# CP_Scheme.net
KiCad netlist of a schematic drawn in Altium Designer
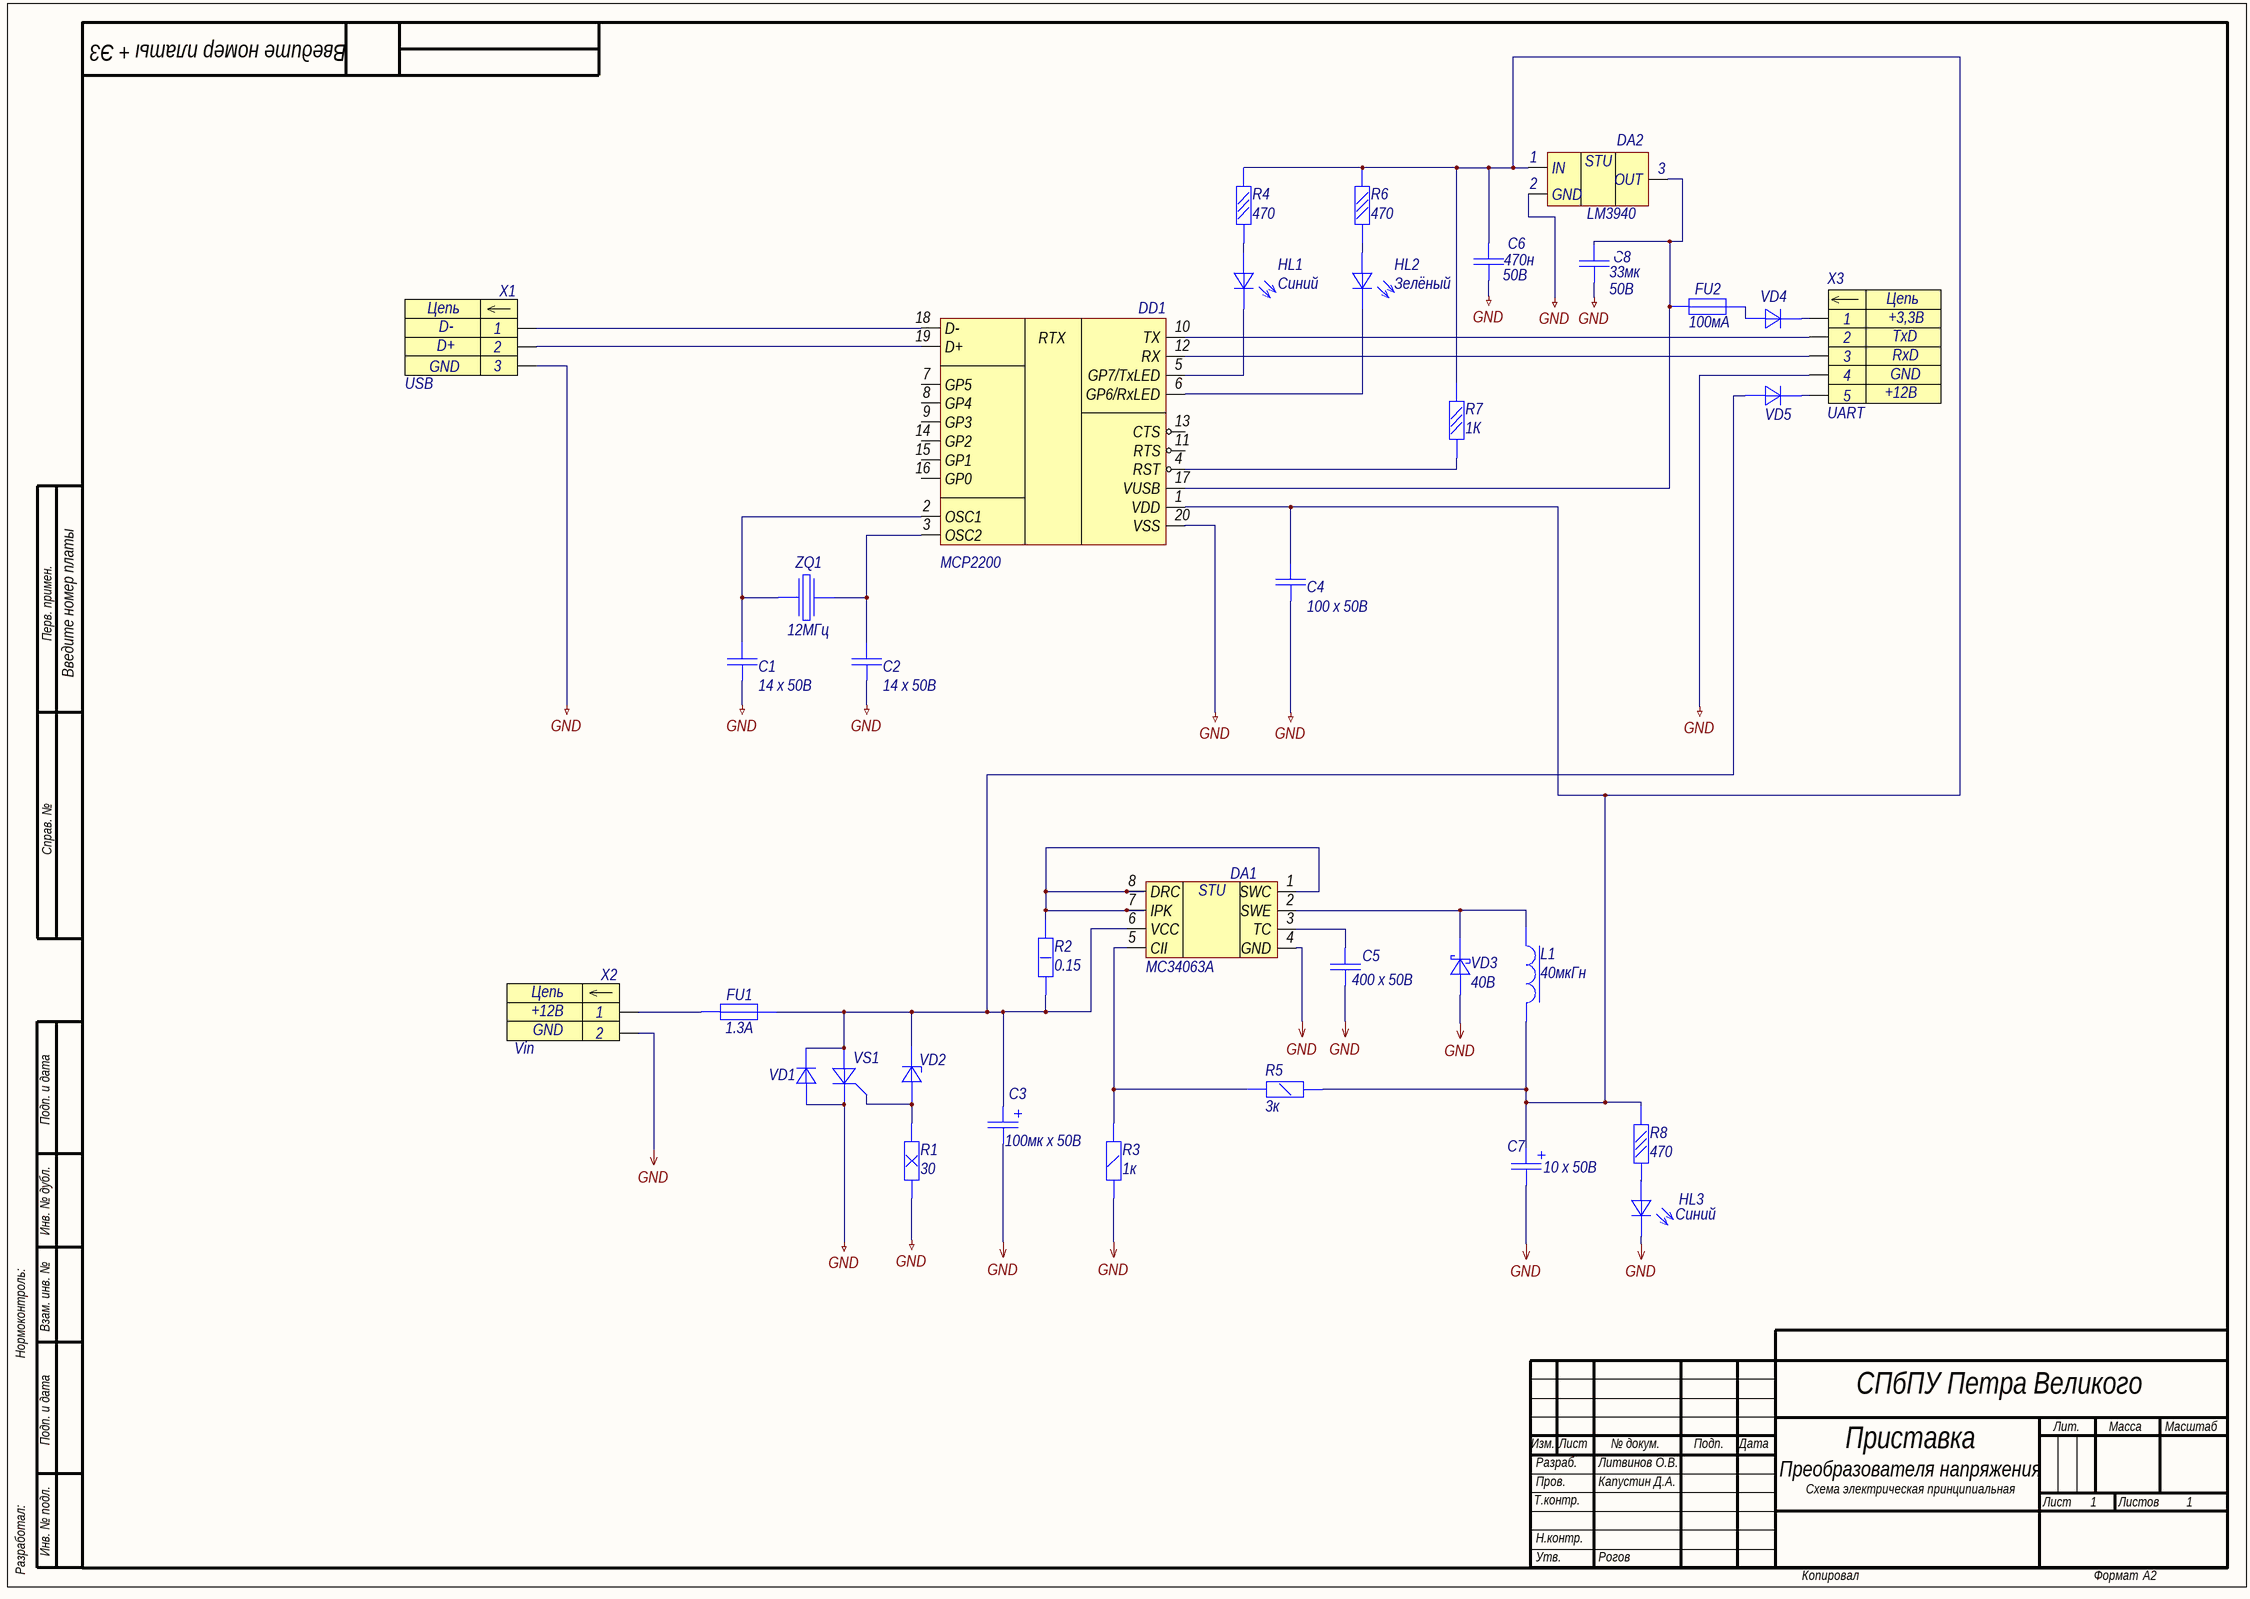
[diagram p0: CP_Scheme.SchDoc]

(export (version "E")
  (design (tool "Eeschema 10.0.6"))
  (components
    (comp (ref "C1")
      (value "14 х 50В")
      (footprint "C0805")
      (fields (field (name "Comment") "Capacitor"))
      (libsource (lib "") (part "Capacitor_1"))
    )
    (comp (ref "C2")
      (value "14 х 50В")
      (footprint "C0805")
      (fields (field (name "Comment") "Capacitor"))
      (libsource (lib "") (part "Capacitor_1"))
    )
    (comp (ref "C3")
      (value "Capacitor-E")
      (footprint "C1206")
      (fields (field (name "ЁМКОСТЬ") "100мк х 50В") (field (name "PUBLISHER") "Олег Литвинов"))
      (libsource (lib "Capacitor GOST") (part "Capacitor-E"))
    )
    (comp (ref "C4")
      (value "100 х 50В")
      (footprint "C0805")
      (fields (field (name "Comment") "Capacitor"))
      (libsource (lib "Capacitor_GOST") (part "Capacitor"))
    )
    (comp (ref "C5")
      (value "Capacitor")
      (footprint "R0805")
      (fields (field (name "ЁМКОСТЬ") "400 х 50В") (field (name "PUBLISHER") "Andrew Danich"))
      (libsource (lib "Capacitor GOST") (part "Capacitor"))
    )
    (comp (ref "C6")
      (value "470н")
      (footprint "C0805")
      (fields (field (name "VOLTAGE") "50В") (field (name "Comment") "Capacitor"))
      (libsource (lib "Capacitor_GOST") (part "Capacitor"))
    )
    (comp (ref "C7")
      (value "Capacitor-E")
      (footprint "C1206")
      (fields (field (name "ЁМКОСТЬ") "10 х 50В") (field (name "PUBLISHER") "Олег Литвинов"))
      (libsource (lib "Capacitor GOST") (part "Capacitor-E"))
    )
    (comp (ref "C8")
      (value "33мк")
      (footprint "C0805")
      (fields (field (name "VOLTAGE") "50В") (field (name "Comment") "Capacitor"))
      (libsource (lib "Capacitor_GOST") (part "Capacitor"))
    )
    (comp (ref "DA1")
      (value "MC34063A")
      (footprint "PCBComponent_1")
      (libsource (lib "MCP2200_UART_USB") (part "MC34063A"))
    )
    (comp (ref "DA2")
      (value "LM3940")
      (footprint "SOT95P237X112-3N")
      (fields (field (name "ITEM ID") "LM3940"))
      (libsource (lib "MCP2200_UART_USB") (part "LM3940"))
    )
    (comp (ref "DD1")
      (value "MCP2200")
      (footprint "SOIC127P1030X265-20N")
      (fields (field (name "WTF") "RTX") (field (name "CREATE") "Litvinov"))
      (libsource (lib "Schlib1") (part "MCP2200"))
    )
    (comp (ref "FU1")
      (value "1.3A")
      (footprint "F1812")
      (fields (field (name "Comment") "Fuse"))
      (libsource (lib "Fuse_GOST") (part "Fuse"))
    )
    (comp (ref "FU2")
      (value "100мA")
      (footprint "F1812")
      (fields (field (name "Comment") "Fuse"))
      (libsource (lib "Fuse_GOST") (part "Fuse"))
    )
    (comp (ref "HL1")
      (value "LED_3V")
      (footprint "LD0805")
      (fields (field (name "ЦВЕТ") "Синий") (field (name "PUBLISHER") "Andrew Danich"))
      (libsource (lib "") (part "Led-1_1"))
    )
    (comp (ref "HL2")
      (value "LED_3V")
      (footprint "LD0805")
      (fields (field (name "ЦВЕТ") "Зелёный") (field (name "PUBLISHER") "Andrew Danich"))
      (libsource (lib "") (part "Led-1_1"))
    )
    (comp (ref "HL3")
      (value "LED_3V")
      (footprint "LD0805")
      (fields (field (name "ЦВЕТ") "Синий") (field (name "PUBLISHER") "Andrew Danich"))
      (libsource (lib "Led GOST") (part "Led-1"))
    )
    (comp (ref "L1")
      (value "40мкГн")
      (footprint "МДГ-2")
      (fields
        (field (name "PART NUMBER") "КИВ18-100")
        (field (name "TOLERANCE") "±10%")
        (field (name "MANUFACTURER") "ОАО \"МСТАТОР\"")
        (field (name "PUBLISHER") "Andrew Danich")
      )
      (libsource (lib "Lib_GOST") (part "Coil"))
    )
    (comp (ref "R1")
      (value "Resistor_10,0W")
      (footprint "R0805")
      (fields (field (name "СОПРОТИВЛЕНИЕ") "30"))
      (libsource (lib "Resistor_GOST") (part "Resistor_10,0W"))
    )
    (comp (ref "R2")
      (value "0.15")
      (footprint "R0805")
      (fields (field (name "Comment") "Resistor_1,0W"))
      (libsource (lib "Resistor_GOST") (part "Resistor_1,0W"))
    )
    (comp (ref "R3")
      (value "1к")
      (footprint "R0805")
      (fields (field (name "Comment") "Resistor_0,25W"))
      (libsource (lib "Resistor_GOST") (part "Resistor_0,25W"))
    )
    (comp (ref "R4")
      (value "Resistor_0,05W")
      (footprint "R0805")
      (fields (field (name "СОПРОТИВЛЕНИЕ") "470"))
      (libsource (lib "Resistor_GOST") (part "Resistor_0,05W"))
    )
    (comp (ref "R5")
      (value "3к")
      (footprint "R0805")
      (fields (field (name "Comment") "Resistor_0,25W"))
      (libsource (lib "Resistor_GOST") (part "Resistor_0,25W"))
    )
    (comp (ref "R6")
      (value "Resistor_0,05W")
      (footprint "R0805")
      (fields (field (name "СОПРОТИВЛЕНИЕ") "470"))
      (libsource (lib "Resistor_GOST") (part "Resistor_0,05W"))
    )
    (comp (ref "R7")
      (value "1К")
      (footprint "R0805")
      (fields (field (name "Comment") "Resistor_0,05W"))
      (libsource (lib "") (part "Resistor_0,05W_1"))
    )
    (comp (ref "R8")
      (value "Resistor_0,05W")
      (footprint "R0805")
      (fields (field (name "СОПРОТИВЛЕНИЕ") "470"))
      (libsource (lib "Resistor_GOST") (part "Resistor_0,05W"))
    )
    (comp (ref "VD1") (value "Diode") (footprint "SOD-123") (libsource (lib "Diode_GOST") (part "Diode")))
    (comp (ref "VD2")
      (value "Suppressor")
      (footprint "DO-214AA")
      (libsource (lib "Diode_GOST") (part "Suppressor"))
    )
    (comp (ref "VD3")
      (value "Schottky")
      (footprint "DO-214AC")
      (description "BYV10-40")
      (fields (field (name "МАКСИМАЛЬНОЕ ОБРАТНОЕ НАПРЯЖЕНИЕ") "40В"))
      (libsource (lib "Diode_GOST") (part "Schottky"))
    )
    (comp (ref "VD4") (value "Diode") (footprint "SOD-123") (libsource (lib "") (part "Diode_2")))
    (comp (ref "VD5") (value "Diode") (footprint "SOD-123") (libsource (lib "") (part "Diode_1")))
    (comp (ref "VS1")
      (value "tiristor")
      (footprint "SOT95P237X112-3N")
      (libsource (lib "Schlib1") (part "tiristor"))
    )
    (comp (ref "X1")
      (value "USB")
      (footprint "DS1099")
      (fields
        (field (name "OUT") "D-")
        (field (name "IN") "D+")
        (field (name "GND") "GND")
        (field (name "CREATE") "DeathSpeaker")
      )
      (libsource (lib "MCP2200_UART_USB") (part "USB_cut"))
    )
    (comp (ref "X2")
      (value "Vin")
      (footprint "DJK-02-Series")
      (fields (field (name "U") "+12В") (field (name "GND") "GND") (field (name "CREATE") "DeathSpeaker"))
      (libsource (lib "MCP2200_UART_USB") (part "Vin"))
    )
    (comp (ref "X3")
      (value "UART")
      (footprint "90136-1x05")
      (fields
        (field (name "GND") "GND")
        (field (name "IN") "TxD")
        (field (name "OUT") "RxD")
        (field (name "U") "+3,3В")
        (field (name "CREATE") "Litvinov")
      )
      (libsource (lib "MCP2200_UART_USB") (part "UART_2"))
    )
    (comp (ref "ZQ1")
      (value "Crystal")
      (footprint "HC-49SM")
      (fields (field (name "ЧАСТОТА") "12МГц") (field (name "PUBLISHER") "Andrew Danich"))
      (libsource (lib "Crystal GOST") (part "Crystal"))
    )
  )
  (nets
    (net (code "1") (name "GND") (class "Default")
      (node (ref "C1") (pin "1") (pinfunction "1_1") (pintype "passive"))
      (node (ref "C2") (pin "1") (pinfunction "1_1") (pintype "passive"))
      (node (ref "C3") (pin "2") (pinfunction "2_2") (pintype "passive"))
      (node (ref "C4") (pin "2") (pinfunction "2_2") (pintype "passive"))
      (node (ref "C5") (pin "1") (pinfunction "1_1") (pintype "passive"))
      (node (ref "C6") (pin "2") (pinfunction "2_2") (pintype "passive"))
      (node (ref "C7") (pin "2") (pinfunction "2_2") (pintype "passive"))
      (node (ref "C8") (pin "2") (pinfunction "2_2") (pintype "passive"))
      (node (ref "DA1") (pin "4") (pinfunction "GND_4") (pintype "passive"))
      (node (ref "DA2") (pin "2") (pinfunction "GND_2") (pintype "passive"))
      (node (ref "DD1") (pin "20") (pinfunction "VSS_20") (pintype "passive"))
      (node (ref "HL3") (pin "2") (pinfunction "К_2") (pintype "passive"))
      (node (ref "R1") (pin "1") (pinfunction "1_1") (pintype "passive"))
      (node (ref "R3") (pin "1") (pinfunction "1_1") (pintype "passive"))
      (node (ref "VD1") (pin "1") (pinfunction "А_1") (pintype "passive"))
      (node (ref "VD3") (pin "1") (pinfunction "А_1") (pintype "passive"))
      (node (ref "VS1") (pin "3") (pinfunction "К_3") (pintype "passive"))
      (node (ref "X1") (pin "3") (pinfunction "3_3") (pintype "passive"))
      (node (ref "X2") (pin "2") (pinfunction "2_2") (pintype "passive"))
      (node (ref "X3") (pin "4") (pinfunction "4_4") (pintype "passive"))
    )
    (net (code "2") (name "Net-(DA1-CII)") (class "Default")
      (node (ref "DA1") (pin "5") (pinfunction "CII_5") (pintype "passive"))
      (node (ref "R3") (pin "2") (pinfunction "2_2") (pintype "passive"))
      (node (ref "R5") (pin "1") (pinfunction "1_1") (pintype "passive"))
    )
    (net (code "3") (name "Net-(DA1-DRC)") (class "Default")
      (node (ref "DA1") (pin "1") (pinfunction "SWC_1") (pintype "passive"))
      (node (ref "DA1") (pin "7") (pinfunction "IPK_7") (pintype "passive"))
      (node (ref "DA1") (pin "8") (pinfunction "DRC_8") (pintype "passive"))
      (node (ref "R2") (pin "2") (pinfunction "2_2") (pintype "passive"))
    )
    (net (code "4") (name "Net-(DA1-SWE)") (class "Default")
      (node (ref "DA1") (pin "2") (pinfunction "SWE_2") (pintype "passive"))
      (node (ref "L1") (pin "1") (pinfunction "1_1") (pintype "passive"))
      (node (ref "VD3") (pin "2") (pinfunction "К_2") (pintype "passive"))
    )
    (net (code "5") (name "Net-(DA1-TC)") (class "Default")
      (node (ref "C5") (pin "2") (pinfunction "2_2") (pintype "passive"))
      (node (ref "DA1") (pin "3") (pinfunction "TC_3") (pintype "passive"))
    )
    (net (code "6") (name "Net-(DA1-VCC)") (class "Default")
      (node (ref "C3") (pin "1") (pinfunction "1_1") (pintype "passive"))
      (node (ref "DA1") (pin "6") (pinfunction "VCC_6") (pintype "passive"))
      (node (ref "FU1") (pin "2") (pinfunction "2_2") (pintype "passive"))
      (node (ref "R2") (pin "1") (pinfunction "1_1") (pintype "passive"))
      (node (ref "VD1") (pin "2") (pinfunction "К_2") (pintype "passive"))
      (node (ref "VD2") (pin "2") (pinfunction "К_2") (pintype "passive"))
      (node (ref "VD5") (pin "1") (pinfunction "А_1") (pintype "passive"))
      (node (ref "VS1") (pin "2") (pinfunction "А_2") (pintype "passive"))
    )
    (net (code "7") (name "Net-(DA2-IN)") (class "Default")
      (node (ref "C4") (pin "1") (pinfunction "1_1") (pintype "passive"))
      (node (ref "C6") (pin "1") (pinfunction "1_1") (pintype "passive"))
      (node (ref "C7") (pin "1") (pinfunction "1_1") (pintype "passive"))
      (node (ref "DA2") (pin "1") (pinfunction "IN_1") (pintype "passive"))
      (node (ref "DD1") (pin "1") (pinfunction "VDD_1") (pintype "passive"))
      (node (ref "L1") (pin "2") (pinfunction "2_2") (pintype "passive"))
      (node (ref "R4") (pin "2") (pinfunction "2_2") (pintype "passive"))
      (node (ref "R5") (pin "2") (pinfunction "2_2") (pintype "passive"))
      (node (ref "R6") (pin "2") (pinfunction "2_2") (pintype "passive"))
      (node (ref "R7") (pin "2") (pinfunction "2_2") (pintype "passive"))
      (node (ref "R8") (pin "2") (pinfunction "2_2") (pintype "passive"))
    )
    (net (code "8") (name "Net-(DA2-OUT)") (class "Default")
      (node (ref "C8") (pin "1") (pinfunction "1_1") (pintype "passive"))
      (node (ref "DA2") (pin "3") (pinfunction "OUT_3") (pintype "passive"))
      (node (ref "DD1") (pin "17") (pinfunction "VUSB_17") (pintype "passive"))
      (node (ref "FU2") (pin "1") (pinfunction "1_1") (pintype "passive"))
    )
    (net (code "9") (name "Net-(DD1-D+)") (class "Default")
      (node (ref "DD1") (pin "19") (pinfunction "D+_19") (pintype "passive"))
      (node (ref "X1") (pin "2") (pinfunction "2_2") (pintype "passive"))
    )
    (net (code "10") (name "Net-(DD1-D-)") (class "Default")
      (node (ref "DD1") (pin "18") (pinfunction "D-_18") (pintype "passive"))
      (node (ref "X1") (pin "1") (pinfunction "1_1") (pintype "passive"))
    )
    (net (code "11") (name "Net-(DD1-GP6{slash}RxLED)") (class "Default")
      (node (ref "DD1") (pin "6") (pinfunction "GP6/RxLED_6") (pintype "passive"))
      (node (ref "HL2") (pin "2") (pinfunction "К_2") (pintype "passive"))
    )
    (net (code "12") (name "Net-(DD1-GP7{slash}TxLED)") (class "Default")
      (node (ref "DD1") (pin "5") (pinfunction "GP7/TxLED_5") (pintype "passive"))
      (node (ref "HL1") (pin "2") (pinfunction "К_2") (pintype "passive"))
    )
    (net (code "13") (name "Net-(DD1-OSC1)") (class "Default")
      (node (ref "C1") (pin "2") (pinfunction "2_2") (pintype "passive"))
      (node (ref "DD1") (pin "2") (pinfunction "OSC1_2") (pintype "passive"))
      (node (ref "ZQ1") (pin "1") (pinfunction "1_1") (pintype "passive"))
    )
    (net (code "14") (name "Net-(DD1-OSC2)") (class "Default")
      (node (ref "C2") (pin "2") (pinfunction "2_2") (pintype "passive"))
      (node (ref "DD1") (pin "3") (pinfunction "OSC2_3") (pintype "passive"))
      (node (ref "ZQ1") (pin "3") (pinfunction "3_3") (pintype "passive"))
    )
    (net (code "15") (name "Net-(DD1-RST)") (class "Default")
      (node (ref "DD1") (pin "4") (pinfunction "RST_4") (pintype "passive"))
      (node (ref "R7") (pin "1") (pinfunction "1_1") (pintype "passive"))
    )
    (net (code "16") (name "Net-(DD1-RX)") (class "Default")
      (node (ref "DD1") (pin "12") (pinfunction "RX_12") (pintype "passive"))
      (node (ref "X3") (pin "3") (pinfunction "3_3") (pintype "passive"))
    )
    (net (code "17") (name "Net-(DD1-TX)") (class "Default")
      (node (ref "DD1") (pin "10") (pinfunction "TX_10") (pintype "passive"))
      (node (ref "X3") (pin "2") (pinfunction "2_2") (pintype "passive"))
    )
    (net (code "18") (name "Net-(FU1-Pad1)") (class "Default")
      (node (ref "FU1") (pin "1") (pinfunction "1_1") (pintype "passive"))
      (node (ref "X2") (pin "1") (pinfunction "1_1") (pintype "passive"))
    )
    (net (code "19") (name "Net-(HL1-А)") (class "Default")
      (node (ref "HL1") (pin "1") (pinfunction "А_1") (pintype "passive"))
      (node (ref "R4") (pin "1") (pinfunction "1_1") (pintype "passive"))
    )
    (net (code "20") (name "Net-(HL2-А)") (class "Default")
      (node (ref "HL2") (pin "1") (pinfunction "А_1") (pintype "passive"))
      (node (ref "R6") (pin "1") (pinfunction "1_1") (pintype "passive"))
    )
    (net (code "21") (name "Net-(HL3-А)") (class "Default")
      (node (ref "HL3") (pin "1") (pinfunction "А_1") (pintype "passive"))
      (node (ref "R8") (pin "1") (pinfunction "1_1") (pintype "passive"))
    )
    (net (code "22") (name "Net-(VD2-А)") (class "Default")
      (node (ref "R1") (pin "2") (pinfunction "2_2") (pintype "passive"))
      (node (ref "VD2") (pin "1") (pinfunction "А_1") (pintype "passive"))
      (node (ref "VS1") (pin "1") (pinfunction "G_1") (pintype "passive"))
    )
    (net (code "23") (name "Net-(VD4-А)") (class "Default")
      (node (ref "FU2") (pin "2") (pinfunction "2_2") (pintype "passive"))
      (node (ref "VD4") (pin "1") (pinfunction "А_1") (pintype "passive"))
    )
    (net (code "24") (name "Net-(VD4-К)") (class "Default")
      (node (ref "VD4") (pin "2") (pinfunction "К_2") (pintype "passive"))
      (node (ref "X3") (pin "1") (pinfunction "1_1") (pintype "passive"))
    )
    (net (code "25") (name "Net-(VD5-К)") (class "Default")
      (node (ref "VD5") (pin "2") (pinfunction "К_2") (pintype "passive"))
      (node (ref "X3") (pin "5") (pinfunction "5_5") (pintype "passive"))
    )
    (net (code "26") (name "unconnected-(DD1-CTS-Pad13)") (class "Default")
      (node (ref "DD1") (pin "13") (pinfunction "CTS_13") (pintype "passive"))
    )
    (net (code "27") (name "unconnected-(DD1-GP0-Pad16)") (class "Default")
      (node (ref "DD1") (pin "16") (pinfunction "GP0_16") (pintype "passive"))
    )
    (net (code "28") (name "unconnected-(DD1-GP1-Pad15)") (class "Default")
      (node (ref "DD1") (pin "15") (pinfunction "GP1_15") (pintype "passive"))
    )
    (net (code "29") (name "unconnected-(DD1-GP2-Pad14)") (class "Default")
      (node (ref "DD1") (pin "14") (pinfunction "GP2_14") (pintype "passive"))
    )
    (net (code "30") (name "unconnected-(DD1-GP3-Pad9)") (class "Default")
      (node (ref "DD1") (pin "9") (pinfunction "GP3_9") (pintype "passive"))
    )
    (net (code "31") (name "unconnected-(DD1-GP4-Pad8)") (class "Default")
      (node (ref "DD1") (pin "8") (pinfunction "GP4_8") (pintype "passive"))
    )
    (net (code "32") (name "unconnected-(DD1-GP5-Pad7)") (class "Default")
      (node (ref "DD1") (pin "7") (pinfunction "GP5_7") (pintype "passive"))
    )
    (net (code "33") (name "unconnected-(DD1-RTS-Pad11)") (class "Default")
      (node (ref "DD1") (pin "11") (pinfunction "RTS_11") (pintype "passive"))
    )
  )
)
